# 2025-10-27.net
KiCad netlist of a schematic drawn in EasyEDA
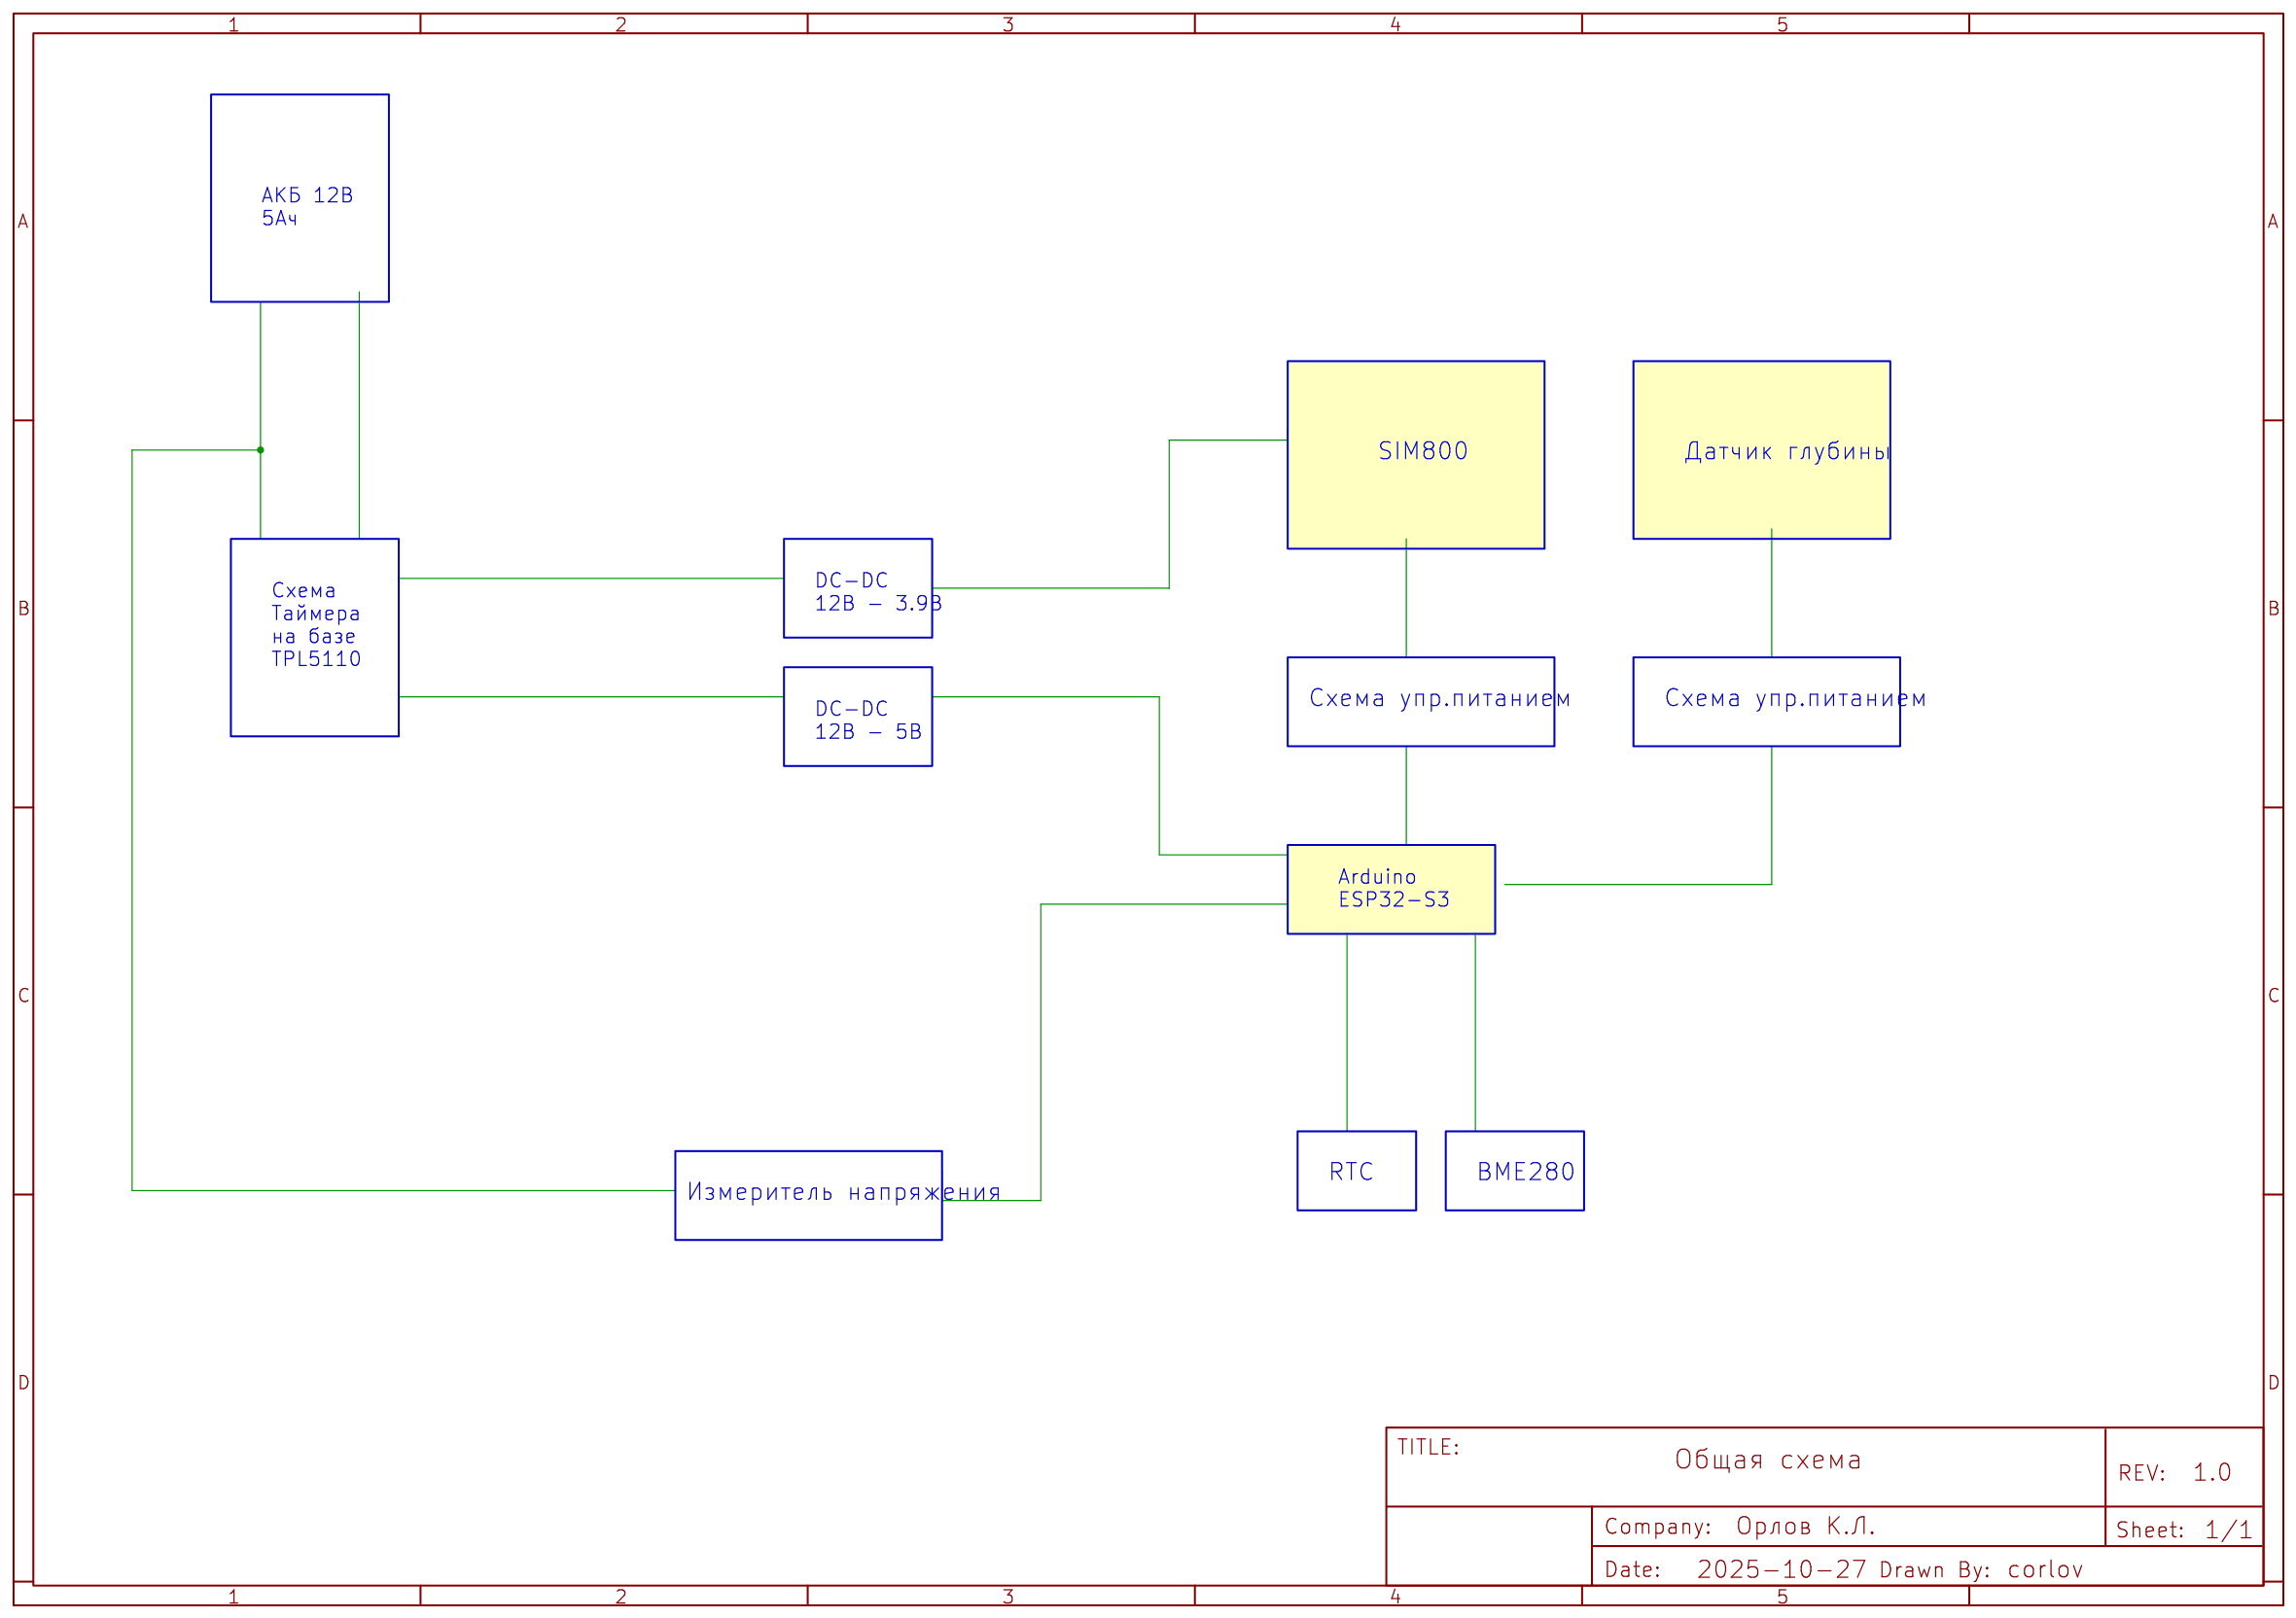
[diagram p0: Общая схема]
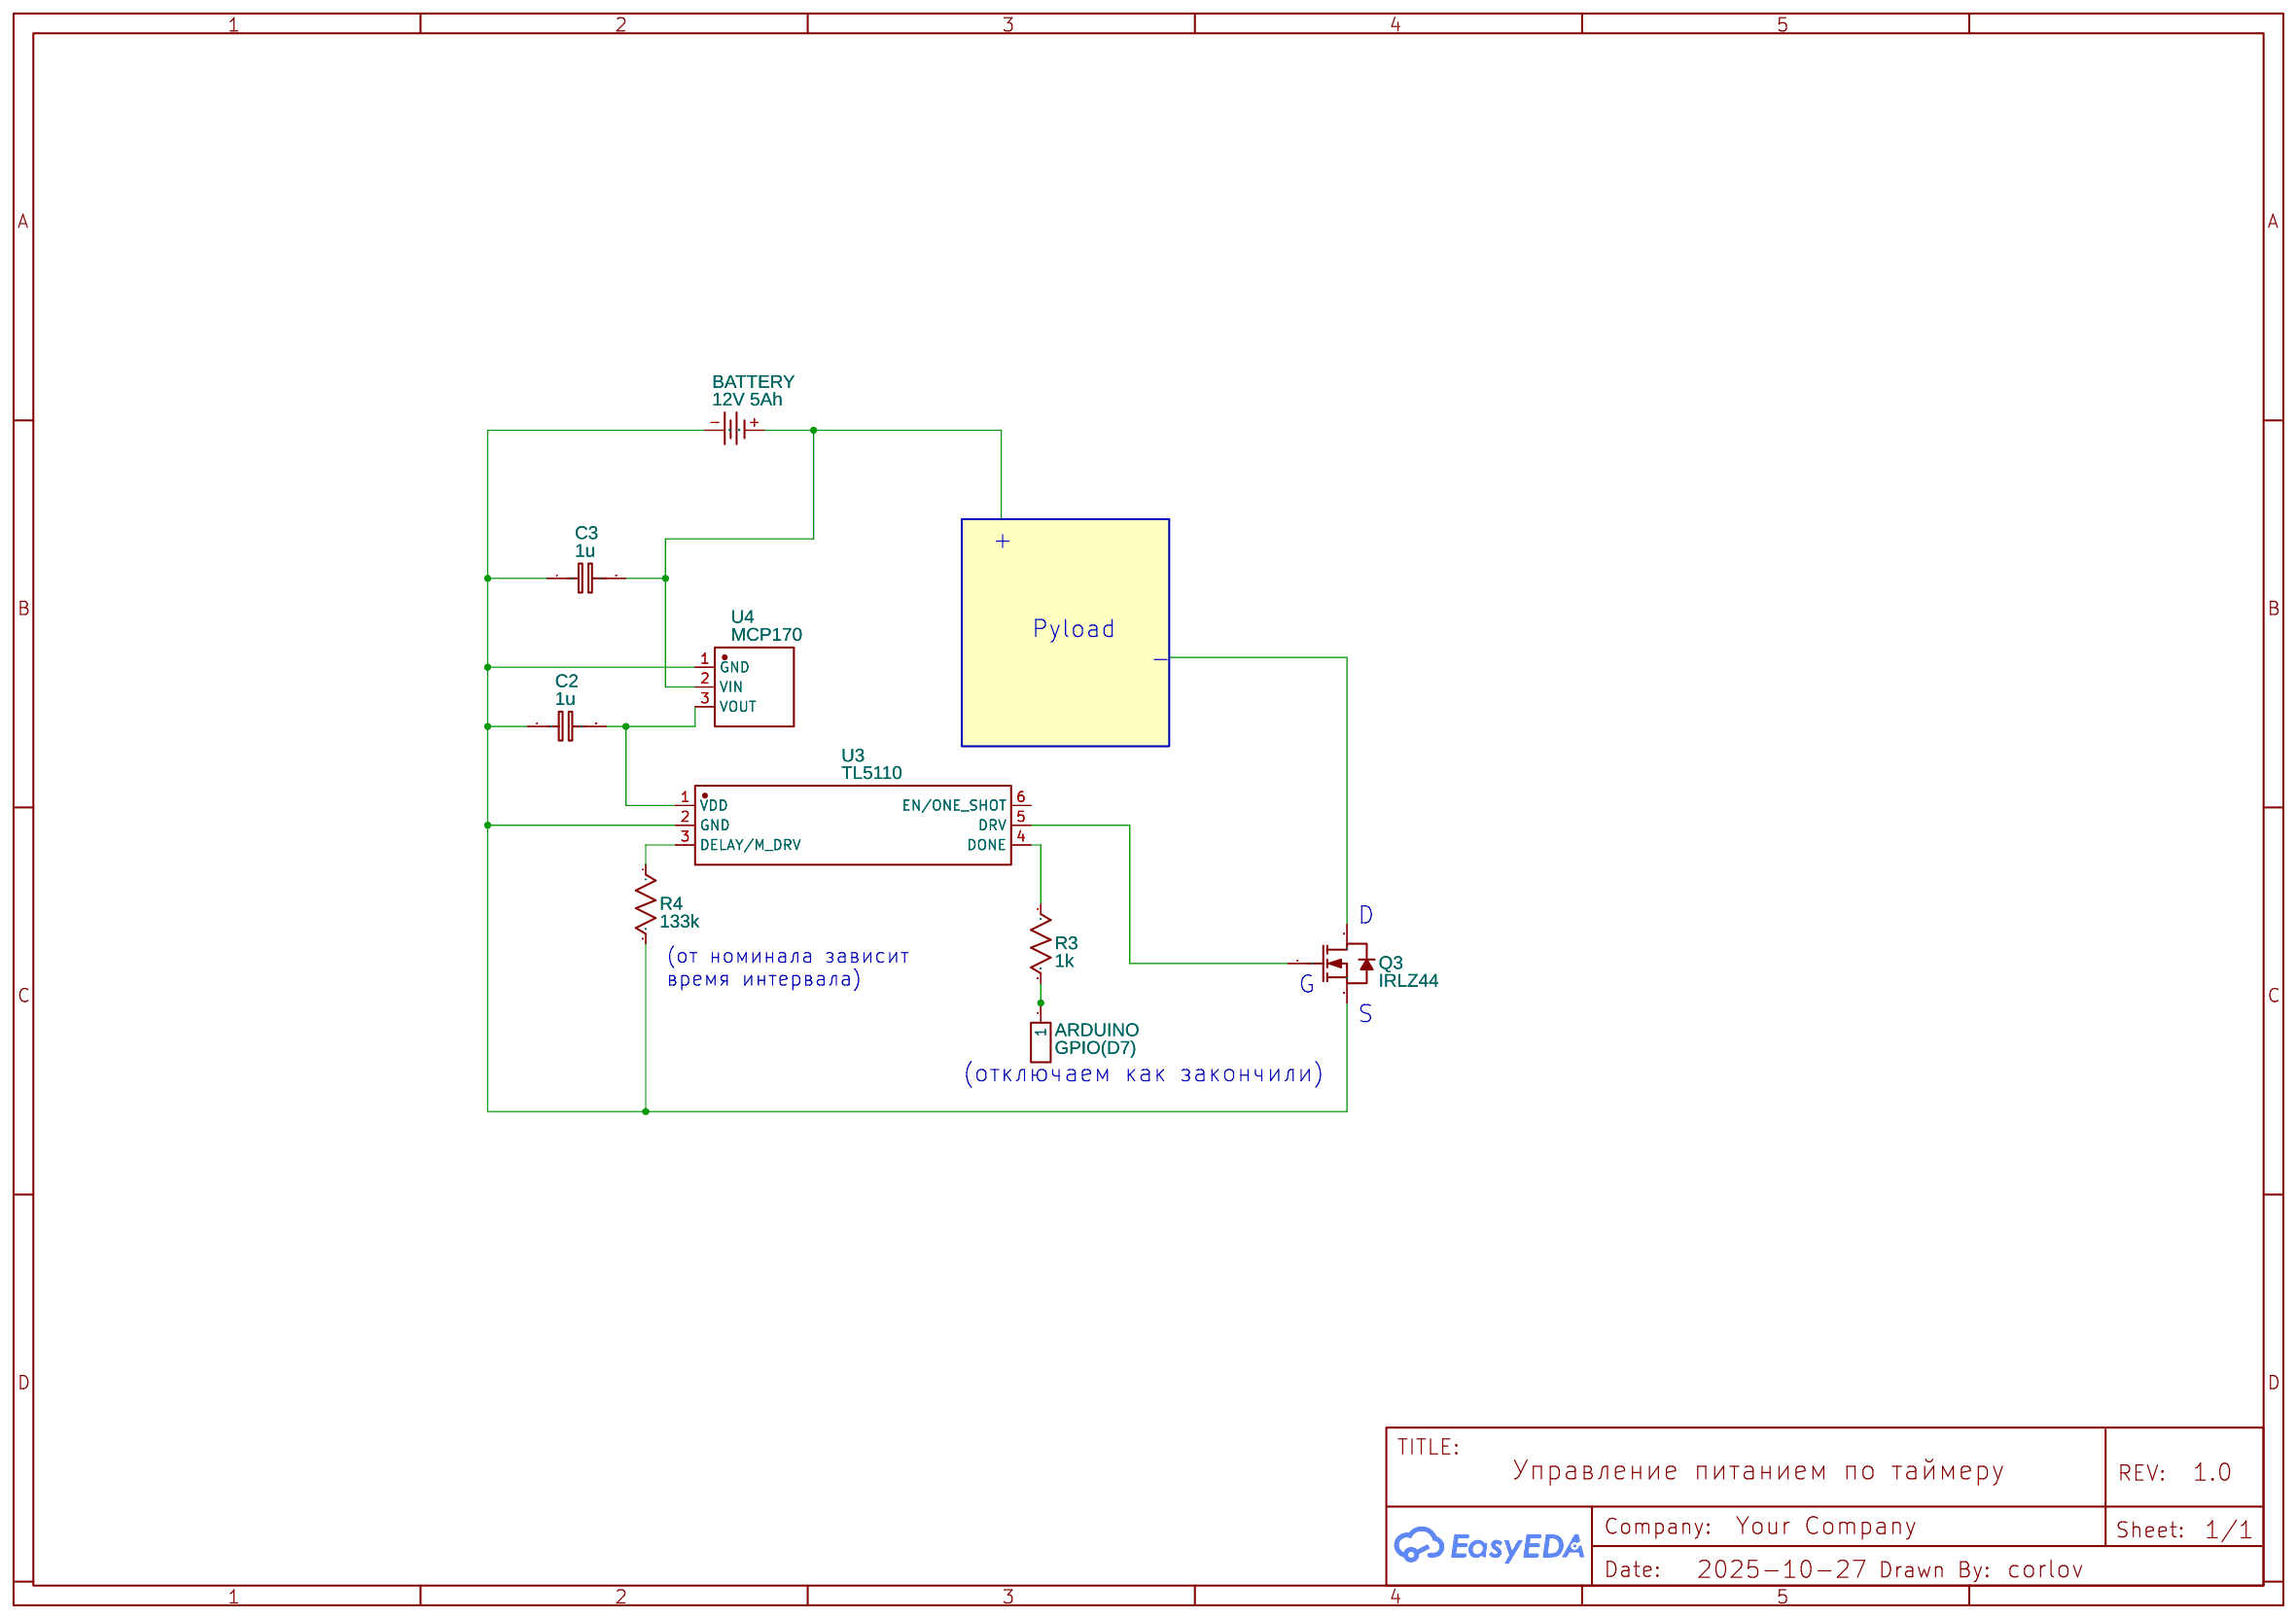
[diagram p1: Питание по атймеру]
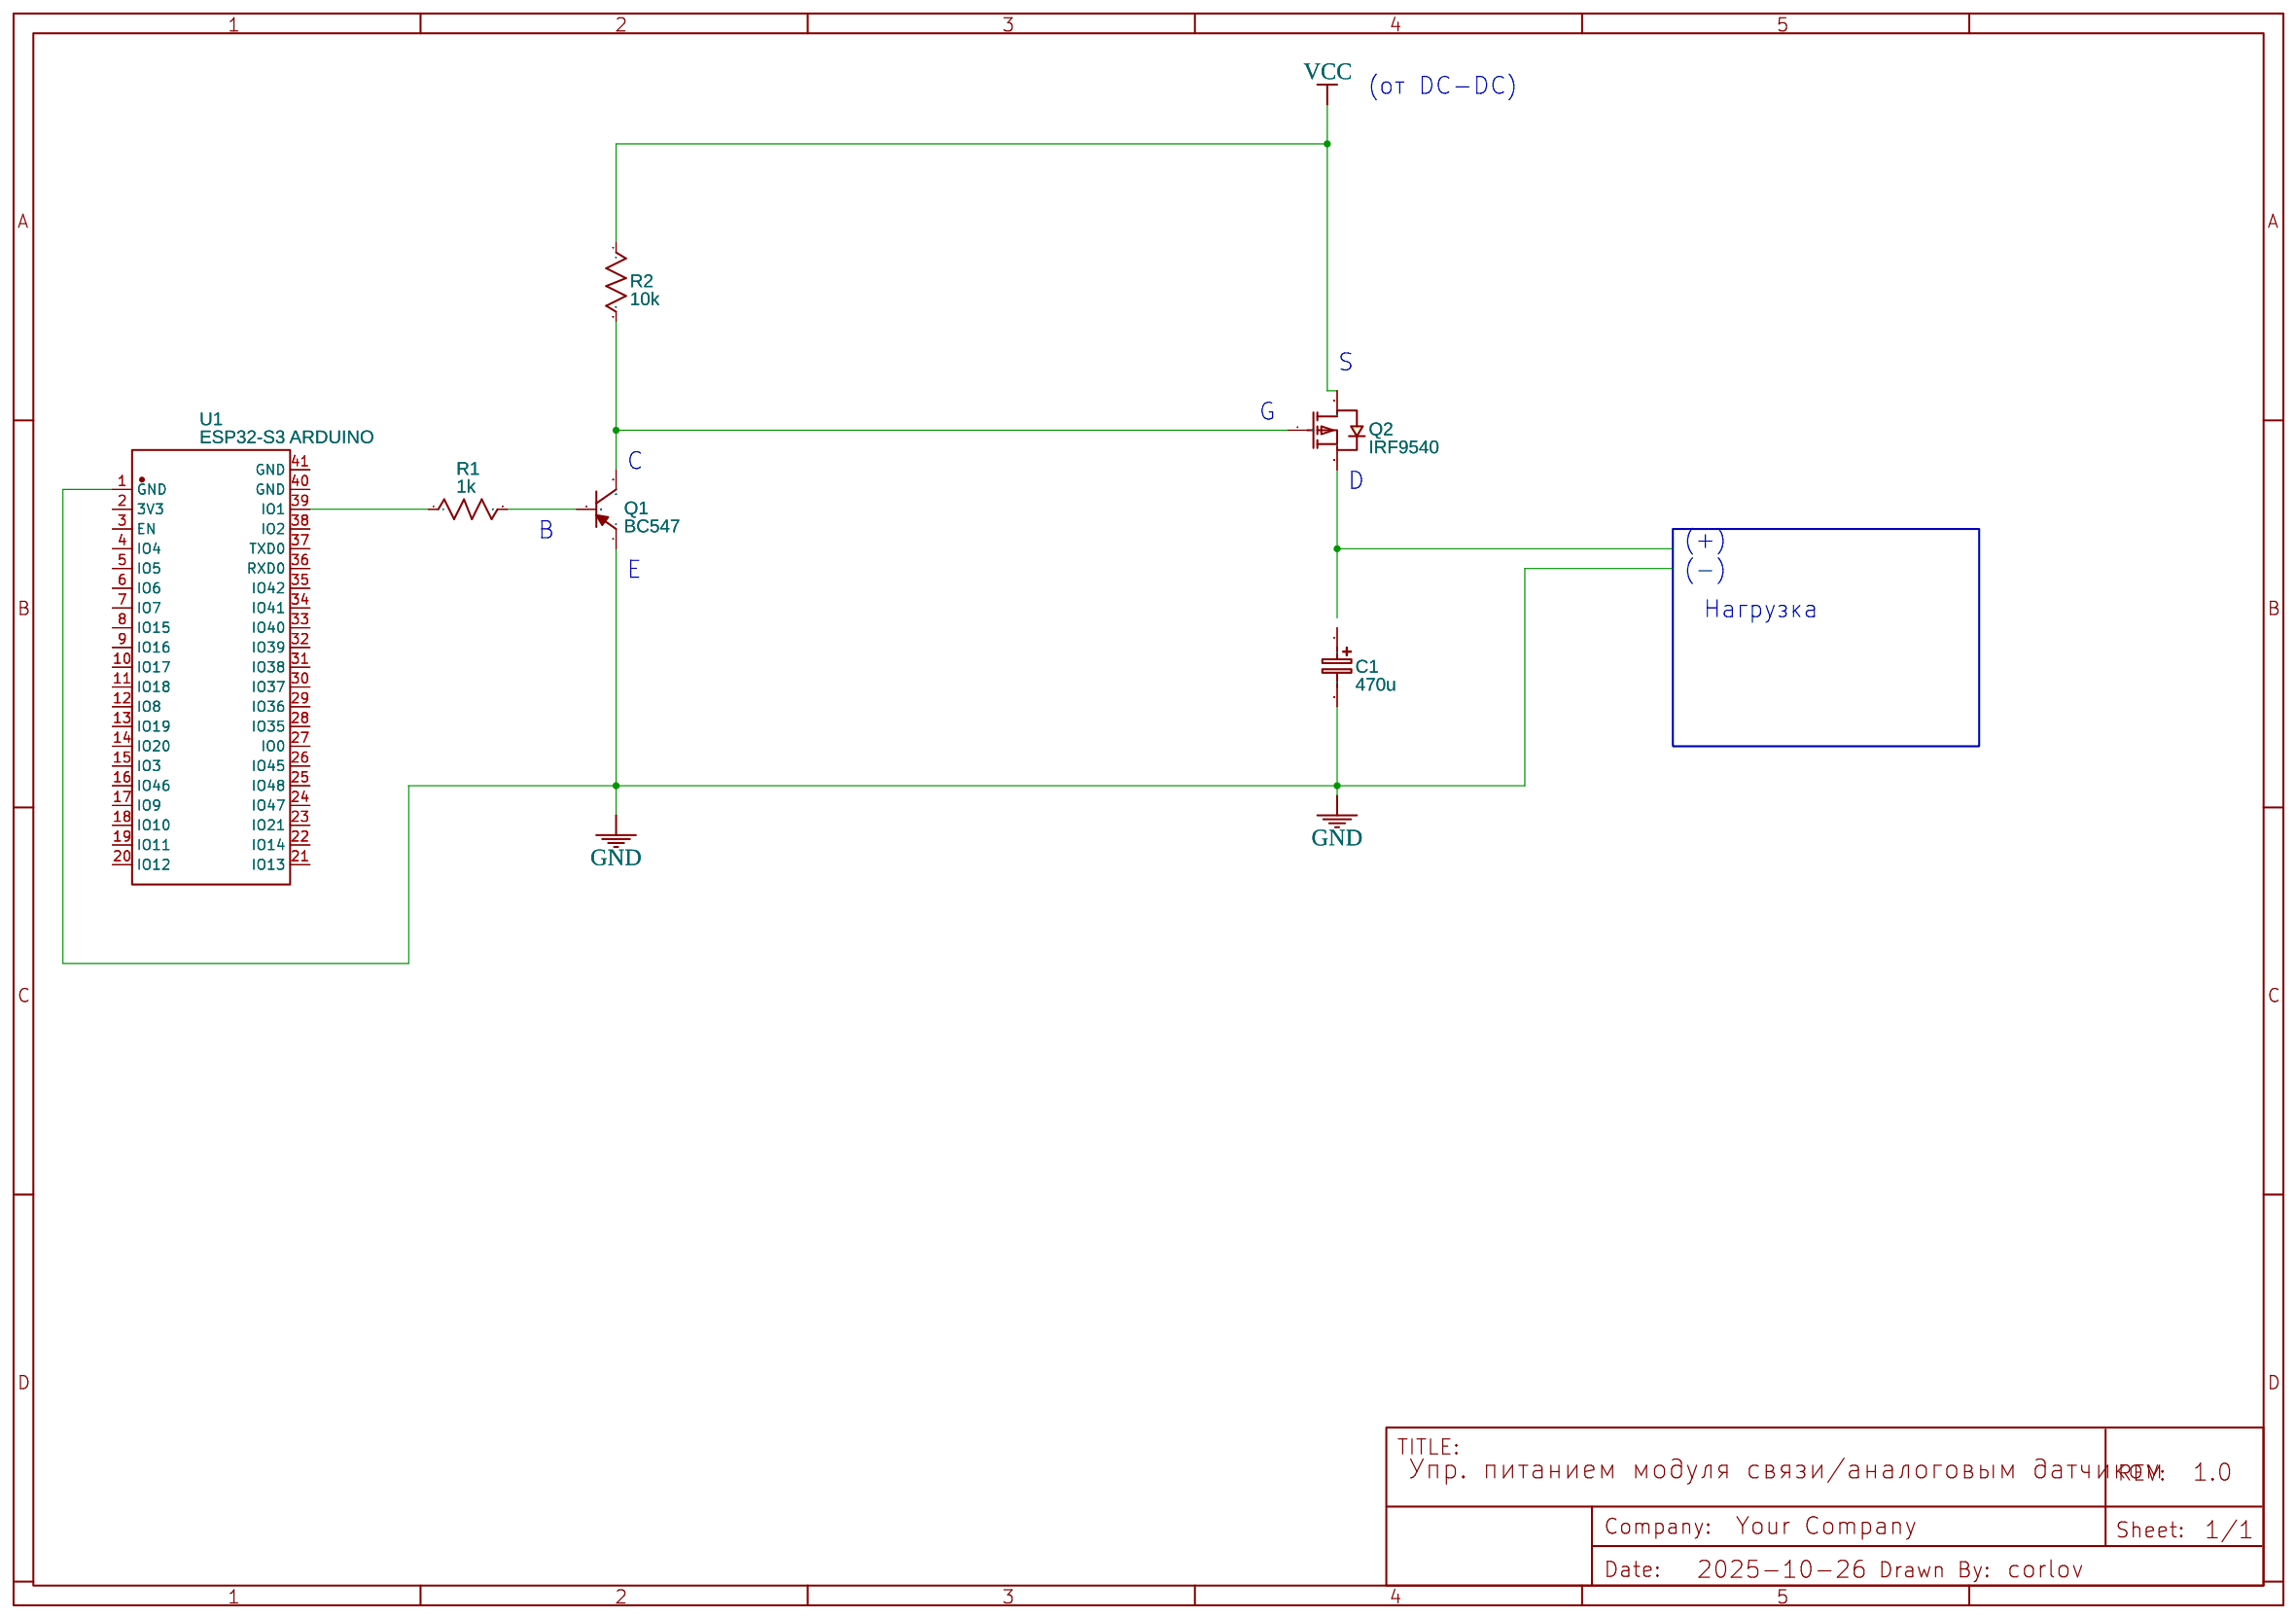
[diagram p2: PowerSwtich]
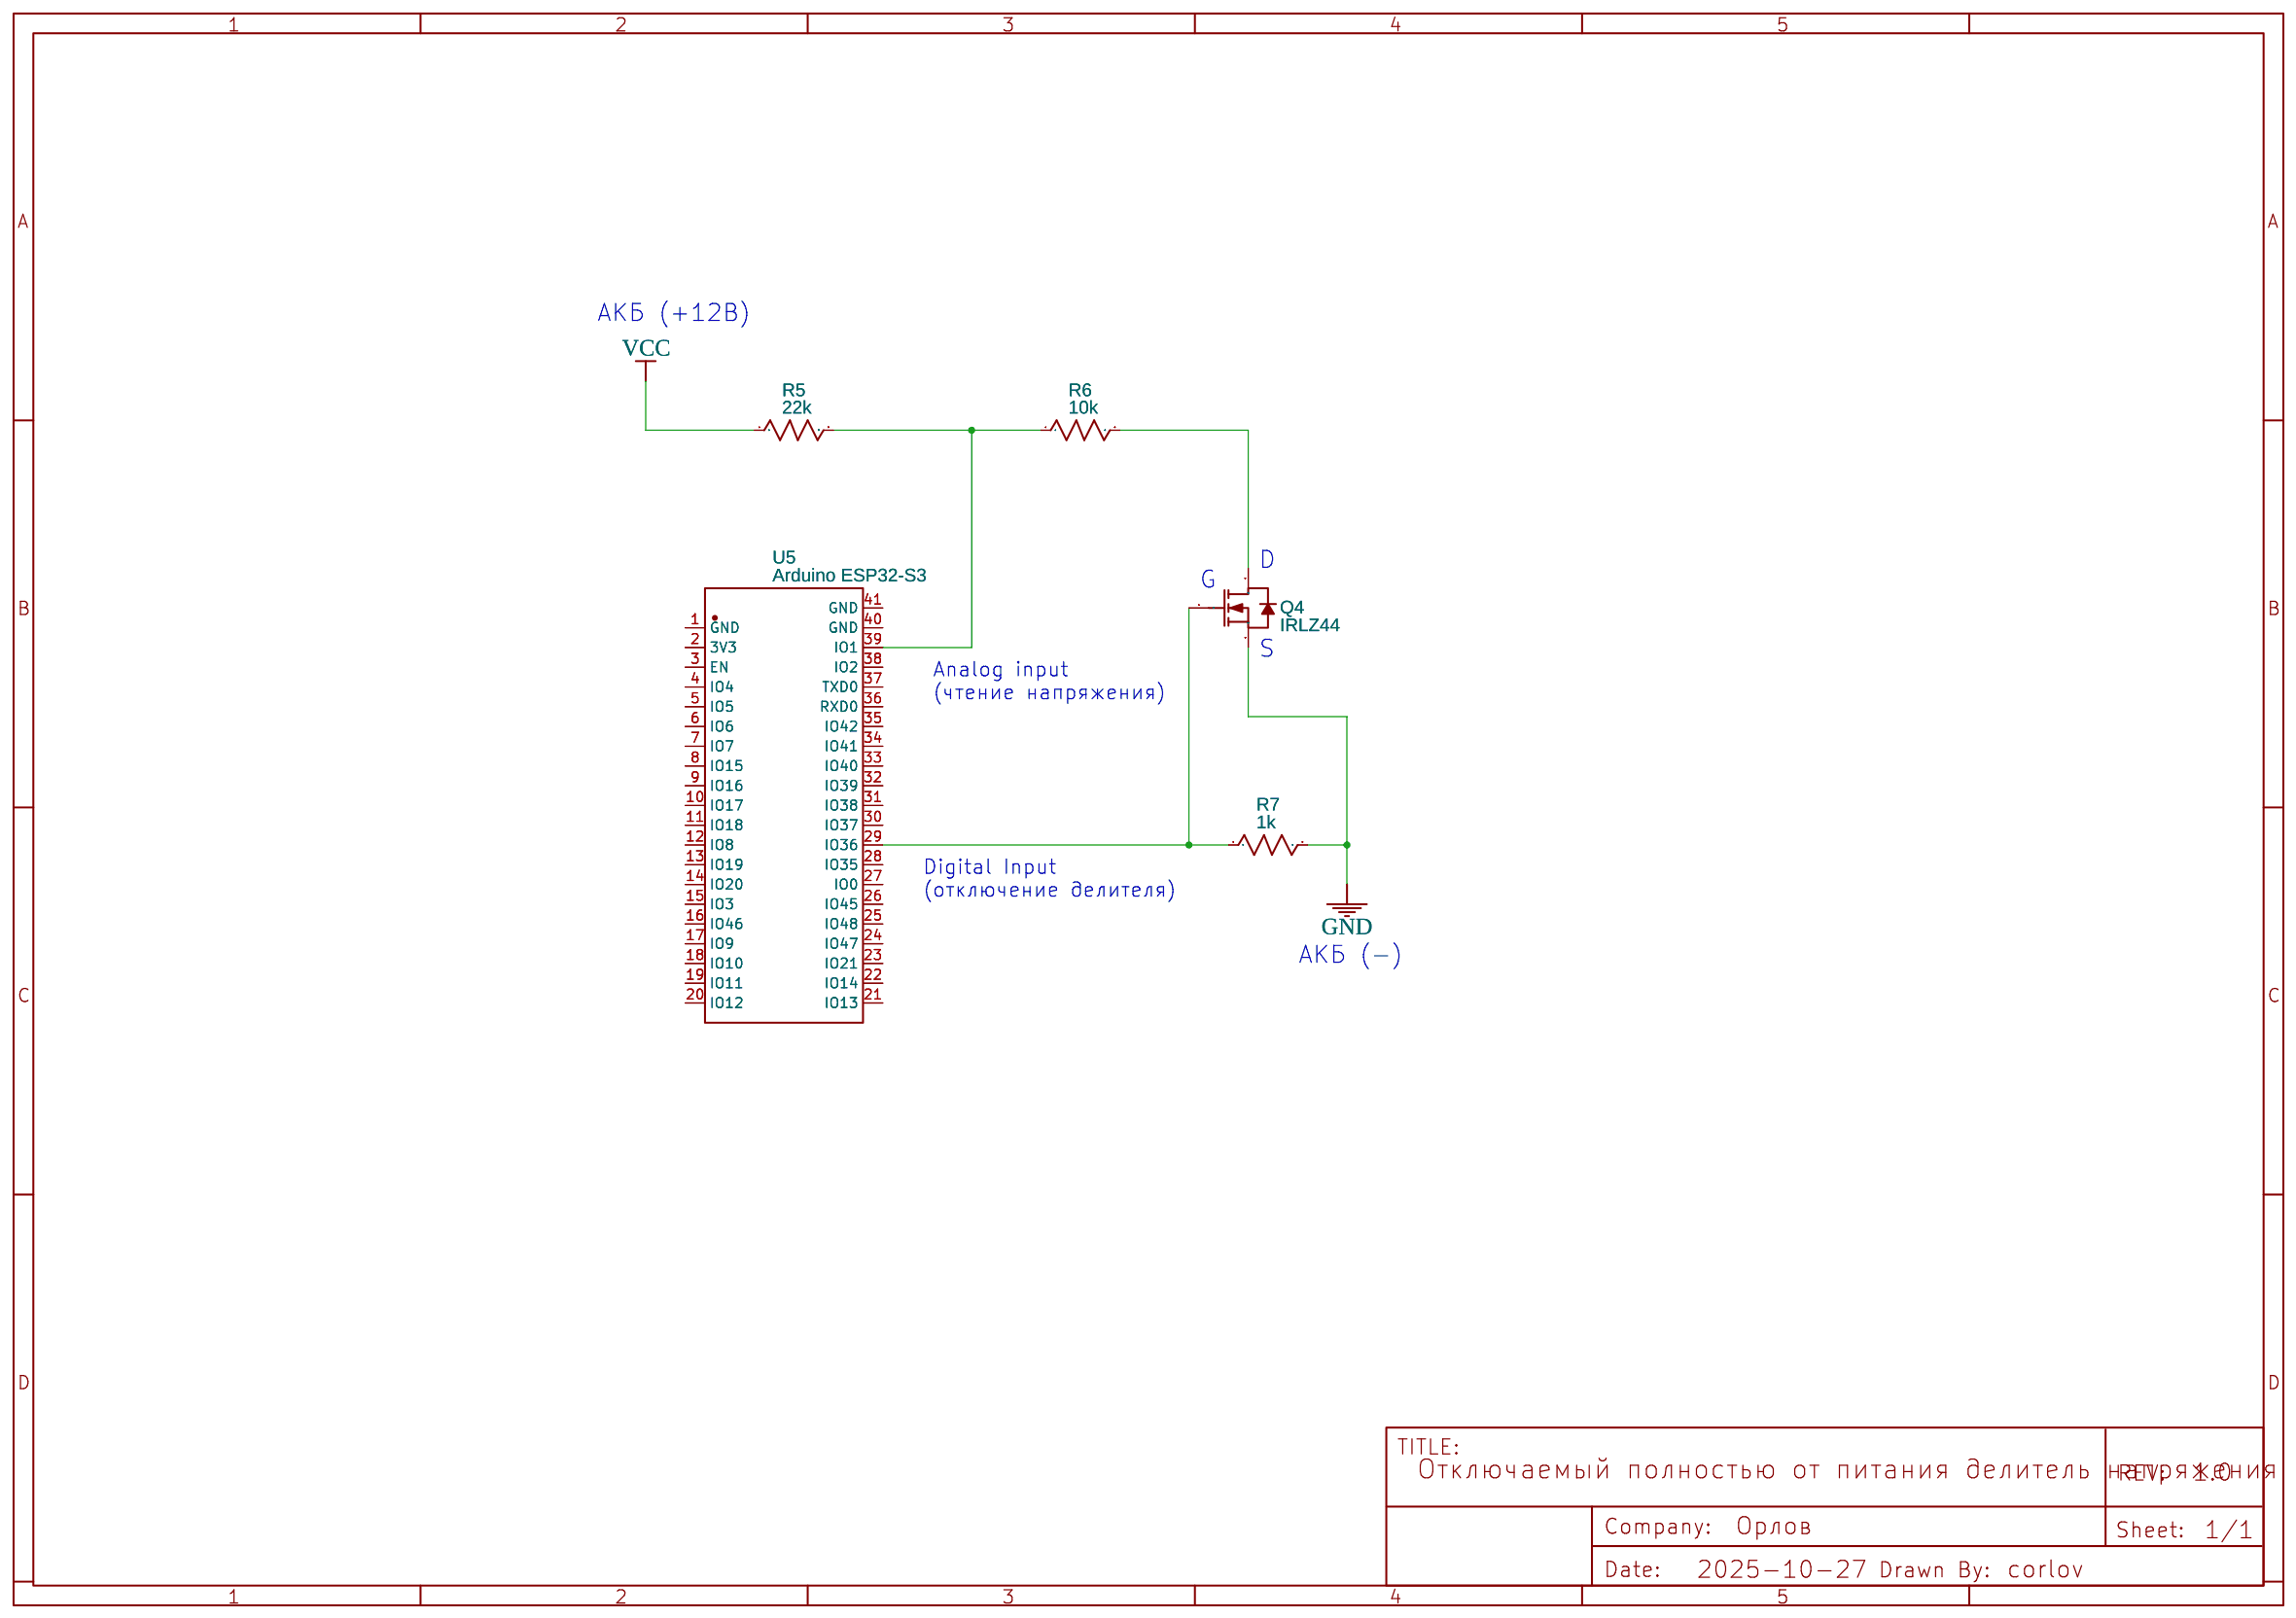
[diagram p3: Отключаемый делитель]

(export (version "E")
  (design (tool "Eeschema 10.0.6"))
  (components
    (comp (ref "ARDUINO") (value "GPIO(D7)") (libsource (lib "") (part "HDR-M-2.54_1x1")))
    (comp (ref "BATTERY")
      (value "12V 5Ah")
      (fields (field (name "Manufacturer Part") "MY-2032-10") (field (name "Manufacturer") "MYOUNG(美阳)"))
      (libsource (lib "") (part "MY-2032-10"))
    )
    (comp (ref "C2") (value "1u") (libsource (lib "") (part "C_0603_EU_1")))
    (comp (ref "C3") (value "1u") (libsource (lib "") (part "C_0603_EU")))
    (comp (ref "Q3")
      (value "IRLZ44")
      (fields (field (name "Manufacturer Part") "IRLZ44NPBF") (field (name "Manufacturer") "Infineon(英飞凌)"))
      (libsource (lib "") (part "IRLZ44NPBF"))
    )
    (comp (ref "R3") (value "1k") (libsource (lib "") (part "R_0603_US")))
    (comp (ref "R4") (value "133k") (libsource (lib "") (part "R_0603_US")))
    (comp (ref "U3")
      (value "TL5110")
      (fields (field (name "Manufacturer Part") "TPL5110DDCR") (field (name "Manufacturer") "TI(德州仪器)"))
      (libsource (lib "") (part "TPL5110DDCR"))
    )
    (comp (ref "U4")
      (value "MCP170")
      (fields
        (field (name "Manufacturer Part") "MCP1701AT-5002I/MB")
        (field (name "Manufacturer") "MICROCHIP(美国微芯)")
      )
      (libsource (lib "") (part "MCP1701AT-5002I/MB"))
    )
    (comp (ref "C1") (value "470u") (libsource (lib "") (part "C_Tan_SMD_A_EU")))
    (comp (ref "Q1")
      (value "BC547")
      (fields (field (name "Manufacturer Part") "2N3906S-RTK/PS") (field (name "Manufacturer") "KEC"))
      (libsource (lib "") (part "2N3906(SOT-23)"))
    )
    (comp (ref "Q2")
      (value "IRF9540")
      (fields (field (name "Manufacturer Part") "IRF5210STRLPBF") (field (name "Manufacturer") "IR"))
      (libsource (lib "") (part "IRF5210"))
    )
    (comp (ref "R1") (value "1k") (libsource (lib "") (part "R_0603_US_1")))
    (comp (ref "R2") (value "10k") (libsource (lib "") (part "R_0603_US")))
    (comp (ref "U1")
      (value "ESP32-S3 ARDUINO")
      (fields (field (name "Manufacturer Part") "ESP32-S3-WROOM-1U"))
      (libsource (lib "") (part "ESP32-S3-WROOM-1U"))
    )
    (comp (ref "Q4")
      (value "IRLZ44")
      (fields (field (name "Manufacturer Part") "IRLZ44NPBF") (field (name "Manufacturer") "Infineon(英飞凌)"))
      (libsource (lib "") (part "IRLZ44NPBF"))
    )
    (comp (ref "R5") (value "22k") (libsource (lib "") (part "R_0603_US")))
    (comp (ref "R6") (value "10k") (libsource (lib "") (part "R_0603_US")))
    (comp (ref "R7") (value "1k") (libsource (lib "") (part "R_0603_US")))
    (comp (ref "U5")
      (value "Arduino ESP32-S3")
      (fields (field (name "Manufacturer Part") "ESP32-S3-WROOM-1U"))
      (libsource (lib "") (part "ESP32-S3-WROOM-1U"))
    )
  )
  (nets
    (net (code "1") (name "GND") (class "Default")
      (node (ref "C1") (pin "2") (pinfunction "2_2") (pintype "unspecified"))
      (node (ref "Q1") (pin "1") (pinfunction "E_1") (pintype "input"))
      (node (ref "Q4") (pin "3") (pinfunction "S_3") (pintype "unspecified"))
      (node (ref "R7") (pin "2") (pinfunction "2_2") (pintype "unspecified"))
      (node (ref "U1") (pin "1") (pinfunction "GND_1") (pintype "unspecified"))
    )
    (net (code "2") (name "Net-(ARDUINO-Pad1)") (class "Default")
      (node (ref "ARDUINO") (pin "1") (pinfunction "1_1") (pintype "input"))
      (node (ref "R3") (pin "2") (pinfunction "2_2") (pintype "unspecified"))
    )
    (net (code "3") (name "Net-(BATTERY-BAT+)") (class "Default")
      (node (ref "BATTERY") (pin "-") (pinfunction "BAT+_-") (pintype "input"))
      (node (ref "C2") (pin "1") (pinfunction "1_1") (pintype "unspecified"))
      (node (ref "C3") (pin "1") (pinfunction "1_1") (pintype "unspecified"))
      (node (ref "Q3") (pin "3") (pinfunction "S_3") (pintype "unspecified"))
      (node (ref "R4") (pin "2") (pinfunction "2_2") (pintype "unspecified"))
      (node (ref "U3") (pin "2") (pinfunction "GND_2") (pintype "unspecified"))
      (node (ref "U4") (pin "1") (pinfunction "GND_1") (pintype "unspecified"))
    )
    (net (code "4") (name "Net-(BATTERY-BAT-)") (class "Default")
      (node (ref "BATTERY") (pin "+") (pinfunction "BAT-_+") (pintype "input"))
      (node (ref "C3") (pin "2") (pinfunction "2_2") (pintype "unspecified"))
      (node (ref "U4") (pin "2") (pinfunction "VIN_2") (pintype "unspecified"))
    )
    (net (code "5") (name "Net-(Q1-B)") (class "Default")
      (node (ref "Q1") (pin "2") (pinfunction "B_2") (pintype "input"))
      (node (ref "R1") (pin "2") (pinfunction "2_2") (pintype "unspecified"))
    )
    (net (code "6") (name "Net-(Q1-C)") (class "Default")
      (node (ref "Q1") (pin "3") (pinfunction "C_3") (pintype "input"))
      (node (ref "Q2") (pin "1") (pinfunction "G_1") (pintype "unspecified"))
      (node (ref "R2") (pin "2") (pinfunction "2_2") (pintype "unspecified"))
    )
    (net (code "7") (name "Net-(Q3-G)") (class "Default")
      (node (ref "Q3") (pin "1") (pinfunction "G_1") (pintype "unspecified"))
      (node (ref "U3") (pin "5") (pinfunction "DRV_5") (pintype "unspecified"))
    )
    (net (code "8") (name "Net-(Q4-D)") (class "Default")
      (node (ref "Q4") (pin "2") (pinfunction "D_2") (pintype "unspecified"))
      (node (ref "R6") (pin "2") (pinfunction "2_2") (pintype "unspecified"))
    )
    (net (code "9") (name "Net-(Q4-G)") (class "Default")
      (node (ref "Q4") (pin "1") (pinfunction "G_1") (pintype "unspecified"))
      (node (ref "R7") (pin "1") (pinfunction "1_1") (pintype "unspecified"))
      (node (ref "U5") (pin "29") (pinfunction "IO36_29") (pintype "unspecified"))
    )
    (net (code "10") (name "Net-(U1-IO1)") (class "Default")
      (node (ref "R1") (pin "1") (pinfunction "1_1") (pintype "unspecified"))
      (node (ref "U1") (pin "39") (pinfunction "IO1_39") (pintype "unspecified"))
    )
    (net (code "11") (name "Net-(U3-DELAY{slash}M_DRV)") (class "Default")
      (node (ref "R4") (pin "1") (pinfunction "1_1") (pintype "unspecified"))
      (node (ref "U3") (pin "3") (pinfunction "DELAY/M_DRV_3") (pintype "unspecified"))
    )
    (net (code "12") (name "Net-(U3-DONE)") (class "Default")
      (node (ref "R3") (pin "1") (pinfunction "1_1") (pintype "unspecified"))
      (node (ref "U3") (pin "4") (pinfunction "DONE_4") (pintype "unspecified"))
    )
    (net (code "13") (name "Net-(U3-VDD)") (class "Default")
      (node (ref "C2") (pin "2") (pinfunction "2_2") (pintype "unspecified"))
      (node (ref "U3") (pin "1") (pinfunction "VDD_1") (pintype "unspecified"))
      (node (ref "U4") (pin "3") (pinfunction "VOUT_3") (pintype "unspecified"))
    )
    (net (code "14") (name "Net-(U5-IO1)") (class "Default")
      (node (ref "R5") (pin "2") (pinfunction "2_2") (pintype "unspecified"))
      (node (ref "R6") (pin "1") (pinfunction "1_1") (pintype "unspecified"))
      (node (ref "U5") (pin "39") (pinfunction "IO1_39") (pintype "unspecified"))
    )
    (net (code "15") (name "VCC") (class "Default")
      (node (ref "Q2") (pin "4") (pinfunction "D_4") (pintype "unspecified"))
      (node (ref "R2") (pin "1") (pinfunction "1_1") (pintype "unspecified"))
      (node (ref "R5") (pin "1") (pinfunction "1_1") (pintype "unspecified"))
    )
    (net (code "16") (name "unconnected-(C1-Pad1)") (class "Default")
      (node (ref "C1") (pin "1") (pinfunction "1_1") (pintype "unspecified"))
    )
    (net (code "17") (name "unconnected-(Q2-S-Pad3)") (class "Default")
      (node (ref "Q2") (pin "3") (pinfunction "S_3") (pintype "unspecified"))
    )
    (net (code "18") (name "unconnected-(Q3-D-Pad2)") (class "Default")
      (node (ref "Q3") (pin "2") (pinfunction "D_2") (pintype "unspecified"))
    )
    (net (code "19") (name "unconnected-(U1-3V3-Pad2)") (class "Default")
      (node (ref "U1") (pin "2") (pinfunction "3V3_2") (pintype "unspecified"))
    )
    (net (code "20") (name "unconnected-(U1-EN-Pad3)") (class "Default")
      (node (ref "U1") (pin "3") (pinfunction "EN_3") (pintype "unspecified"))
    )
    (net (code "21") (name "unconnected-(U1-GND-Pad40)") (class "Default")
      (node (ref "U1") (pin "40") (pinfunction "GND_40") (pintype "unspecified"))
    )
    (net (code "22") (name "unconnected-(U1-GND-Pad41)") (class "Default")
      (node (ref "U1") (pin "41") (pinfunction "GND_41") (pintype "unspecified"))
    )
    (net (code "23") (name "unconnected-(U1-IO0-Pad27)") (class "Default")
      (node (ref "U1") (pin "27") (pinfunction "IO0_27") (pintype "unspecified"))
    )
    (net (code "24") (name "unconnected-(U1-IO2-Pad38)") (class "Default")
      (node (ref "U1") (pin "38") (pinfunction "IO2_38") (pintype "unspecified"))
    )
    (net (code "25") (name "unconnected-(U1-IO3-Pad15)") (class "Default")
      (node (ref "U1") (pin "15") (pinfunction "IO3_15") (pintype "unspecified"))
    )
    (net (code "26") (name "unconnected-(U1-IO4-Pad4)") (class "Default")
      (node (ref "U1") (pin "4") (pinfunction "IO4_4") (pintype "unspecified"))
    )
    (net (code "27") (name "unconnected-(U1-IO5-Pad5)") (class "Default")
      (node (ref "U1") (pin "5") (pinfunction "IO5_5") (pintype "unspecified"))
    )
    (net (code "28") (name "unconnected-(U1-IO6-Pad6)") (class "Default")
      (node (ref "U1") (pin "6") (pinfunction "IO6_6") (pintype "unspecified"))
    )
    (net (code "29") (name "unconnected-(U1-IO7-Pad7)") (class "Default")
      (node (ref "U1") (pin "7") (pinfunction "IO7_7") (pintype "unspecified"))
    )
    (net (code "30") (name "unconnected-(U1-IO8-Pad12)") (class "Default")
      (node (ref "U1") (pin "12") (pinfunction "IO8_12") (pintype "unspecified"))
    )
    (net (code "31") (name "unconnected-(U1-IO9-Pad17)") (class "Default")
      (node (ref "U1") (pin "17") (pinfunction "IO9_17") (pintype "unspecified"))
    )
    (net (code "32") (name "unconnected-(U1-IO10-Pad18)") (class "Default")
      (node (ref "U1") (pin "18") (pinfunction "IO10_18") (pintype "unspecified"))
    )
    (net (code "33") (name "unconnected-(U1-IO11-Pad19)") (class "Default")
      (node (ref "U1") (pin "19") (pinfunction "IO11_19") (pintype "unspecified"))
    )
    (net (code "34") (name "unconnected-(U1-IO12-Pad20)") (class "Default")
      (node (ref "U1") (pin "20") (pinfunction "IO12_20") (pintype "unspecified"))
    )
    (net (code "35") (name "unconnected-(U1-IO13-Pad21)") (class "Default")
      (node (ref "U1") (pin "21") (pinfunction "IO13_21") (pintype "unspecified"))
    )
    (net (code "36") (name "unconnected-(U1-IO14-Pad22)") (class "Default")
      (node (ref "U1") (pin "22") (pinfunction "IO14_22") (pintype "unspecified"))
    )
    (net (code "37") (name "unconnected-(U1-IO15-Pad8)") (class "Default")
      (node (ref "U1") (pin "8") (pinfunction "IO15_8") (pintype "unspecified"))
    )
    (net (code "38") (name "unconnected-(U1-IO16-Pad9)") (class "Default")
      (node (ref "U1") (pin "9") (pinfunction "IO16_9") (pintype "unspecified"))
    )
    (net (code "39") (name "unconnected-(U1-IO17-Pad10)") (class "Default")
      (node (ref "U1") (pin "10") (pinfunction "IO17_10") (pintype "unspecified"))
    )
    (net (code "40") (name "unconnected-(U1-IO18-Pad11)") (class "Default")
      (node (ref "U1") (pin "11") (pinfunction "IO18_11") (pintype "unspecified"))
    )
    (net (code "41") (name "unconnected-(U1-IO19-Pad13)") (class "Default")
      (node (ref "U1") (pin "13") (pinfunction "IO19_13") (pintype "unspecified"))
    )
    (net (code "42") (name "unconnected-(U1-IO20-Pad14)") (class "Default")
      (node (ref "U1") (pin "14") (pinfunction "IO20_14") (pintype "unspecified"))
    )
    (net (code "43") (name "unconnected-(U1-IO21-Pad23)") (class "Default")
      (node (ref "U1") (pin "23") (pinfunction "IO21_23") (pintype "unspecified"))
    )
    (net (code "44") (name "unconnected-(U1-IO35-Pad28)") (class "Default")
      (node (ref "U1") (pin "28") (pinfunction "IO35_28") (pintype "unspecified"))
    )
    (net (code "45") (name "unconnected-(U1-IO36-Pad29)") (class "Default")
      (node (ref "U1") (pin "29") (pinfunction "IO36_29") (pintype "unspecified"))
    )
    (net (code "46") (name "unconnected-(U1-IO37-Pad30)") (class "Default")
      (node (ref "U1") (pin "30") (pinfunction "IO37_30") (pintype "unspecified"))
    )
    (net (code "47") (name "unconnected-(U1-IO38-Pad31)") (class "Default")
      (node (ref "U1") (pin "31") (pinfunction "IO38_31") (pintype "unspecified"))
    )
    (net (code "48") (name "unconnected-(U1-IO39-Pad32)") (class "Default")
      (node (ref "U1") (pin "32") (pinfunction "IO39_32") (pintype "unspecified"))
    )
    (net (code "49") (name "unconnected-(U1-IO40-Pad33)") (class "Default")
      (node (ref "U1") (pin "33") (pinfunction "IO40_33") (pintype "unspecified"))
    )
    (net (code "50") (name "unconnected-(U1-IO41-Pad34)") (class "Default")
      (node (ref "U1") (pin "34") (pinfunction "IO41_34") (pintype "unspecified"))
    )
    (net (code "51") (name "unconnected-(U1-IO42-Pad35)") (class "Default")
      (node (ref "U1") (pin "35") (pinfunction "IO42_35") (pintype "unspecified"))
    )
    (net (code "52") (name "unconnected-(U1-IO45-Pad26)") (class "Default")
      (node (ref "U1") (pin "26") (pinfunction "IO45_26") (pintype "unspecified"))
    )
    (net (code "53") (name "unconnected-(U1-IO46-Pad16)") (class "Default")
      (node (ref "U1") (pin "16") (pinfunction "IO46_16") (pintype "unspecified"))
    )
    (net (code "54") (name "unconnected-(U1-IO47-Pad24)") (class "Default")
      (node (ref "U1") (pin "24") (pinfunction "IO47_24") (pintype "unspecified"))
    )
    (net (code "55") (name "unconnected-(U1-IO48-Pad25)") (class "Default")
      (node (ref "U1") (pin "25") (pinfunction "IO48_25") (pintype "unspecified"))
    )
    (net (code "56") (name "unconnected-(U1-RXD0-Pad36)") (class "Default")
      (node (ref "U1") (pin "36") (pinfunction "RXD0_36") (pintype "unspecified"))
    )
    (net (code "57") (name "unconnected-(U1-TXD0-Pad37)") (class "Default")
      (node (ref "U1") (pin "37") (pinfunction "TXD0_37") (pintype "unspecified"))
    )
    (net (code "58") (name "unconnected-(U3-EN{slash}ONE_SHOT-Pad6)") (class "Default")
      (node (ref "U3") (pin "6") (pinfunction "EN/ONE_SHOT_6") (pintype "unspecified"))
    )
    (net (code "59") (name "unconnected-(U5-3V3-Pad2)") (class "Default")
      (node (ref "U5") (pin "2") (pinfunction "3V3_2") (pintype "unspecified"))
    )
    (net (code "60") (name "unconnected-(U5-EN-Pad3)") (class "Default")
      (node (ref "U5") (pin "3") (pinfunction "EN_3") (pintype "unspecified"))
    )
    (net (code "61") (name "unconnected-(U5-GND-Pad1)") (class "Default")
      (node (ref "U5") (pin "1") (pinfunction "GND_1") (pintype "unspecified"))
    )
    (net (code "62") (name "unconnected-(U5-GND-Pad40)") (class "Default")
      (node (ref "U5") (pin "40") (pinfunction "GND_40") (pintype "unspecified"))
    )
    (net (code "63") (name "unconnected-(U5-GND-Pad41)") (class "Default")
      (node (ref "U5") (pin "41") (pinfunction "GND_41") (pintype "unspecified"))
    )
    (net (code "64") (name "unconnected-(U5-IO0-Pad27)") (class "Default")
      (node (ref "U5") (pin "27") (pinfunction "IO0_27") (pintype "unspecified"))
    )
    (net (code "65") (name "unconnected-(U5-IO2-Pad38)") (class "Default")
      (node (ref "U5") (pin "38") (pinfunction "IO2_38") (pintype "unspecified"))
    )
    (net (code "66") (name "unconnected-(U5-IO3-Pad15)") (class "Default")
      (node (ref "U5") (pin "15") (pinfunction "IO3_15") (pintype "unspecified"))
    )
    (net (code "67") (name "unconnected-(U5-IO4-Pad4)") (class "Default")
      (node (ref "U5") (pin "4") (pinfunction "IO4_4") (pintype "unspecified"))
    )
    (net (code "68") (name "unconnected-(U5-IO5-Pad5)") (class "Default")
      (node (ref "U5") (pin "5") (pinfunction "IO5_5") (pintype "unspecified"))
    )
    (net (code "69") (name "unconnected-(U5-IO6-Pad6)") (class "Default")
      (node (ref "U5") (pin "6") (pinfunction "IO6_6") (pintype "unspecified"))
    )
    (net (code "70") (name "unconnected-(U5-IO7-Pad7)") (class "Default")
      (node (ref "U5") (pin "7") (pinfunction "IO7_7") (pintype "unspecified"))
    )
    (net (code "71") (name "unconnected-(U5-IO8-Pad12)") (class "Default")
      (node (ref "U5") (pin "12") (pinfunction "IO8_12") (pintype "unspecified"))
    )
    (net (code "72") (name "unconnected-(U5-IO9-Pad17)") (class "Default")
      (node (ref "U5") (pin "17") (pinfunction "IO9_17") (pintype "unspecified"))
    )
    (net (code "73") (name "unconnected-(U5-IO10-Pad18)") (class "Default")
      (node (ref "U5") (pin "18") (pinfunction "IO10_18") (pintype "unspecified"))
    )
    (net (code "74") (name "unconnected-(U5-IO11-Pad19)") (class "Default")
      (node (ref "U5") (pin "19") (pinfunction "IO11_19") (pintype "unspecified"))
    )
    (net (code "75") (name "unconnected-(U5-IO12-Pad20)") (class "Default")
      (node (ref "U5") (pin "20") (pinfunction "IO12_20") (pintype "unspecified"))
    )
    (net (code "76") (name "unconnected-(U5-IO13-Pad21)") (class "Default")
      (node (ref "U5") (pin "21") (pinfunction "IO13_21") (pintype "unspecified"))
    )
    (net (code "77") (name "unconnected-(U5-IO14-Pad22)") (class "Default")
      (node (ref "U5") (pin "22") (pinfunction "IO14_22") (pintype "unspecified"))
    )
    (net (code "78") (name "unconnected-(U5-IO15-Pad8)") (class "Default")
      (node (ref "U5") (pin "8") (pinfunction "IO15_8") (pintype "unspecified"))
    )
    (net (code "79") (name "unconnected-(U5-IO16-Pad9)") (class "Default")
      (node (ref "U5") (pin "9") (pinfunction "IO16_9") (pintype "unspecified"))
    )
    (net (code "80") (name "unconnected-(U5-IO17-Pad10)") (class "Default")
      (node (ref "U5") (pin "10") (pinfunction "IO17_10") (pintype "unspecified"))
    )
    (net (code "81") (name "unconnected-(U5-IO18-Pad11)") (class "Default")
      (node (ref "U5") (pin "11") (pinfunction "IO18_11") (pintype "unspecified"))
    )
    (net (code "82") (name "unconnected-(U5-IO19-Pad13)") (class "Default")
      (node (ref "U5") (pin "13") (pinfunction "IO19_13") (pintype "unspecified"))
    )
    (net (code "83") (name "unconnected-(U5-IO20-Pad14)") (class "Default")
      (node (ref "U5") (pin "14") (pinfunction "IO20_14") (pintype "unspecified"))
    )
    (net (code "84") (name "unconnected-(U5-IO21-Pad23)") (class "Default")
      (node (ref "U5") (pin "23") (pinfunction "IO21_23") (pintype "unspecified"))
    )
    (net (code "85") (name "unconnected-(U5-IO35-Pad28)") (class "Default")
      (node (ref "U5") (pin "28") (pinfunction "IO35_28") (pintype "unspecified"))
    )
    (net (code "86") (name "unconnected-(U5-IO37-Pad30)") (class "Default")
      (node (ref "U5") (pin "30") (pinfunction "IO37_30") (pintype "unspecified"))
    )
    (net (code "87") (name "unconnected-(U5-IO38-Pad31)") (class "Default")
      (node (ref "U5") (pin "31") (pinfunction "IO38_31") (pintype "unspecified"))
    )
    (net (code "88") (name "unconnected-(U5-IO39-Pad32)") (class "Default")
      (node (ref "U5") (pin "32") (pinfunction "IO39_32") (pintype "unspecified"))
    )
    (net (code "89") (name "unconnected-(U5-IO40-Pad33)") (class "Default")
      (node (ref "U5") (pin "33") (pinfunction "IO40_33") (pintype "unspecified"))
    )
    (net (code "90") (name "unconnected-(U5-IO41-Pad34)") (class "Default")
      (node (ref "U5") (pin "34") (pinfunction "IO41_34") (pintype "unspecified"))
    )
    (net (code "91") (name "unconnected-(U5-IO42-Pad35)") (class "Default")
      (node (ref "U5") (pin "35") (pinfunction "IO42_35") (pintype "unspecified"))
    )
    (net (code "92") (name "unconnected-(U5-IO45-Pad26)") (class "Default")
      (node (ref "U5") (pin "26") (pinfunction "IO45_26") (pintype "unspecified"))
    )
    (net (code "93") (name "unconnected-(U5-IO46-Pad16)") (class "Default")
      (node (ref "U5") (pin "16") (pinfunction "IO46_16") (pintype "unspecified"))
    )
    (net (code "94") (name "unconnected-(U5-IO47-Pad24)") (class "Default")
      (node (ref "U5") (pin "24") (pinfunction "IO47_24") (pintype "unspecified"))
    )
    (net (code "95") (name "unconnected-(U5-IO48-Pad25)") (class "Default")
      (node (ref "U5") (pin "25") (pinfunction "IO48_25") (pintype "unspecified"))
    )
    (net (code "96") (name "unconnected-(U5-RXD0-Pad36)") (class "Default")
      (node (ref "U5") (pin "36") (pinfunction "RXD0_36") (pintype "unspecified"))
    )
    (net (code "97") (name "unconnected-(U5-TXD0-Pad37)") (class "Default")
      (node (ref "U5") (pin "37") (pinfunction "TXD0_37") (pintype "unspecified"))
    )
  )
)
